# magnetic_switch_sos_v1-2022.net
KiCad netlist of a schematic drawn in EAGLE
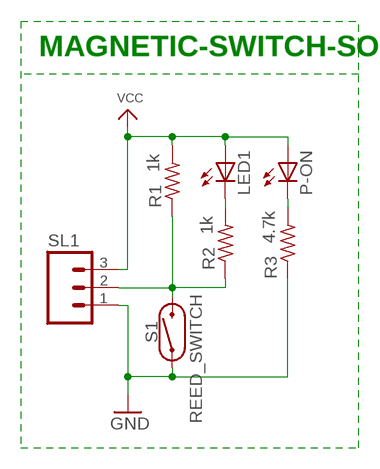
[diagram p0: schematic, sheet 1]

(export (version "E")
  (design (tool "Eeschema 10.0.6"))
  (components
    (comp (ref "LED1")
      (value "LED3MM")
      (footprint "eagle-import:LED3MM")
      (libsource (lib "eagle-import") (part "LED3MM"))
    )
    (comp (ref "P-ON")
      (value "LED3MM")
      (footprint "eagle-import:LED3MM")
      (libsource (lib "eagle-import") (part "LED3MM"))
    )
    (comp (ref "R1")
      (value "1k")
      (footprint "eagle-import:0207_7")
      (libsource (lib "eagle-import") (part "RESISTOR0207/7"))
    )
    (comp (ref "R2")
      (value "1k")
      (footprint "eagle-import:0207_7")
      (libsource (lib "eagle-import") (part "RESISTOR0207/7"))
    )
    (comp (ref "R3")
      (value "4.7k")
      (footprint "eagle-import:0207_7")
      (libsource (lib "eagle-import") (part "RESISTOR0207/7"))
    )
    (comp (ref "S1")
      (value "REED_SWITCH")
      (footprint "eagle-import:REED_SWITCH_GLASS")
      (libsource (lib "eagle-import") (part "REED_SWITCH-PTH-GLASS"))
    )
    (comp (ref "SL1")
      (value "M03")
      (footprint "eagle-import:03P")
      (libsource (lib "eagle-import") (part "M03"))
    )
  )
  (nets
    (net (code "1") (name "GND") (class "Default")
      (node (ref "R3") (pin "1") (pinfunction "1_1") (pintype "passive"))
      (node (ref "S1") (pin "P$1") (pinfunction "1_P$1") (pintype "passive"))
      (node (ref "SL1") (pin "1") (pinfunction "1_1") (pintype "passive"))
    )
    (net (code "2") (name "Net-(LED1-C)") (class "Default")
      (node (ref "LED1") (pin "K") (pinfunction "C_K") (pintype "passive"))
      (node (ref "R2") (pin "2") (pinfunction "2_2") (pintype "passive"))
    )
    (net (code "3") (name "Net-(P-ON-C)") (class "Default")
      (node (ref "P-ON") (pin "K") (pinfunction "C_K") (pintype "passive"))
      (node (ref "R3") (pin "2") (pinfunction "2_2") (pintype "passive"))
    )
    (net (code "4") (name "Net-(S1-2)") (class "Default")
      (node (ref "R1") (pin "1") (pinfunction "1_1") (pintype "passive"))
      (node (ref "R2") (pin "1") (pinfunction "1_1") (pintype "passive"))
      (node (ref "S1") (pin "P$2") (pinfunction "2_P$2") (pintype "passive"))
      (node (ref "SL1") (pin "2") (pinfunction "2_2") (pintype "passive"))
    )
    (net (code "5") (name "VCC") (class "Default")
      (node (ref "LED1") (pin "A") (pinfunction "A_A") (pintype "passive"))
      (node (ref "P-ON") (pin "A") (pinfunction "A_A") (pintype "passive"))
      (node (ref "R1") (pin "2") (pinfunction "2_2") (pintype "passive"))
      (node (ref "SL1") (pin "3") (pinfunction "3_3") (pintype "passive"))
    )
  )
)
